# Nano_XBee.net
KiCad netlist of a schematic drawn in EAGLE
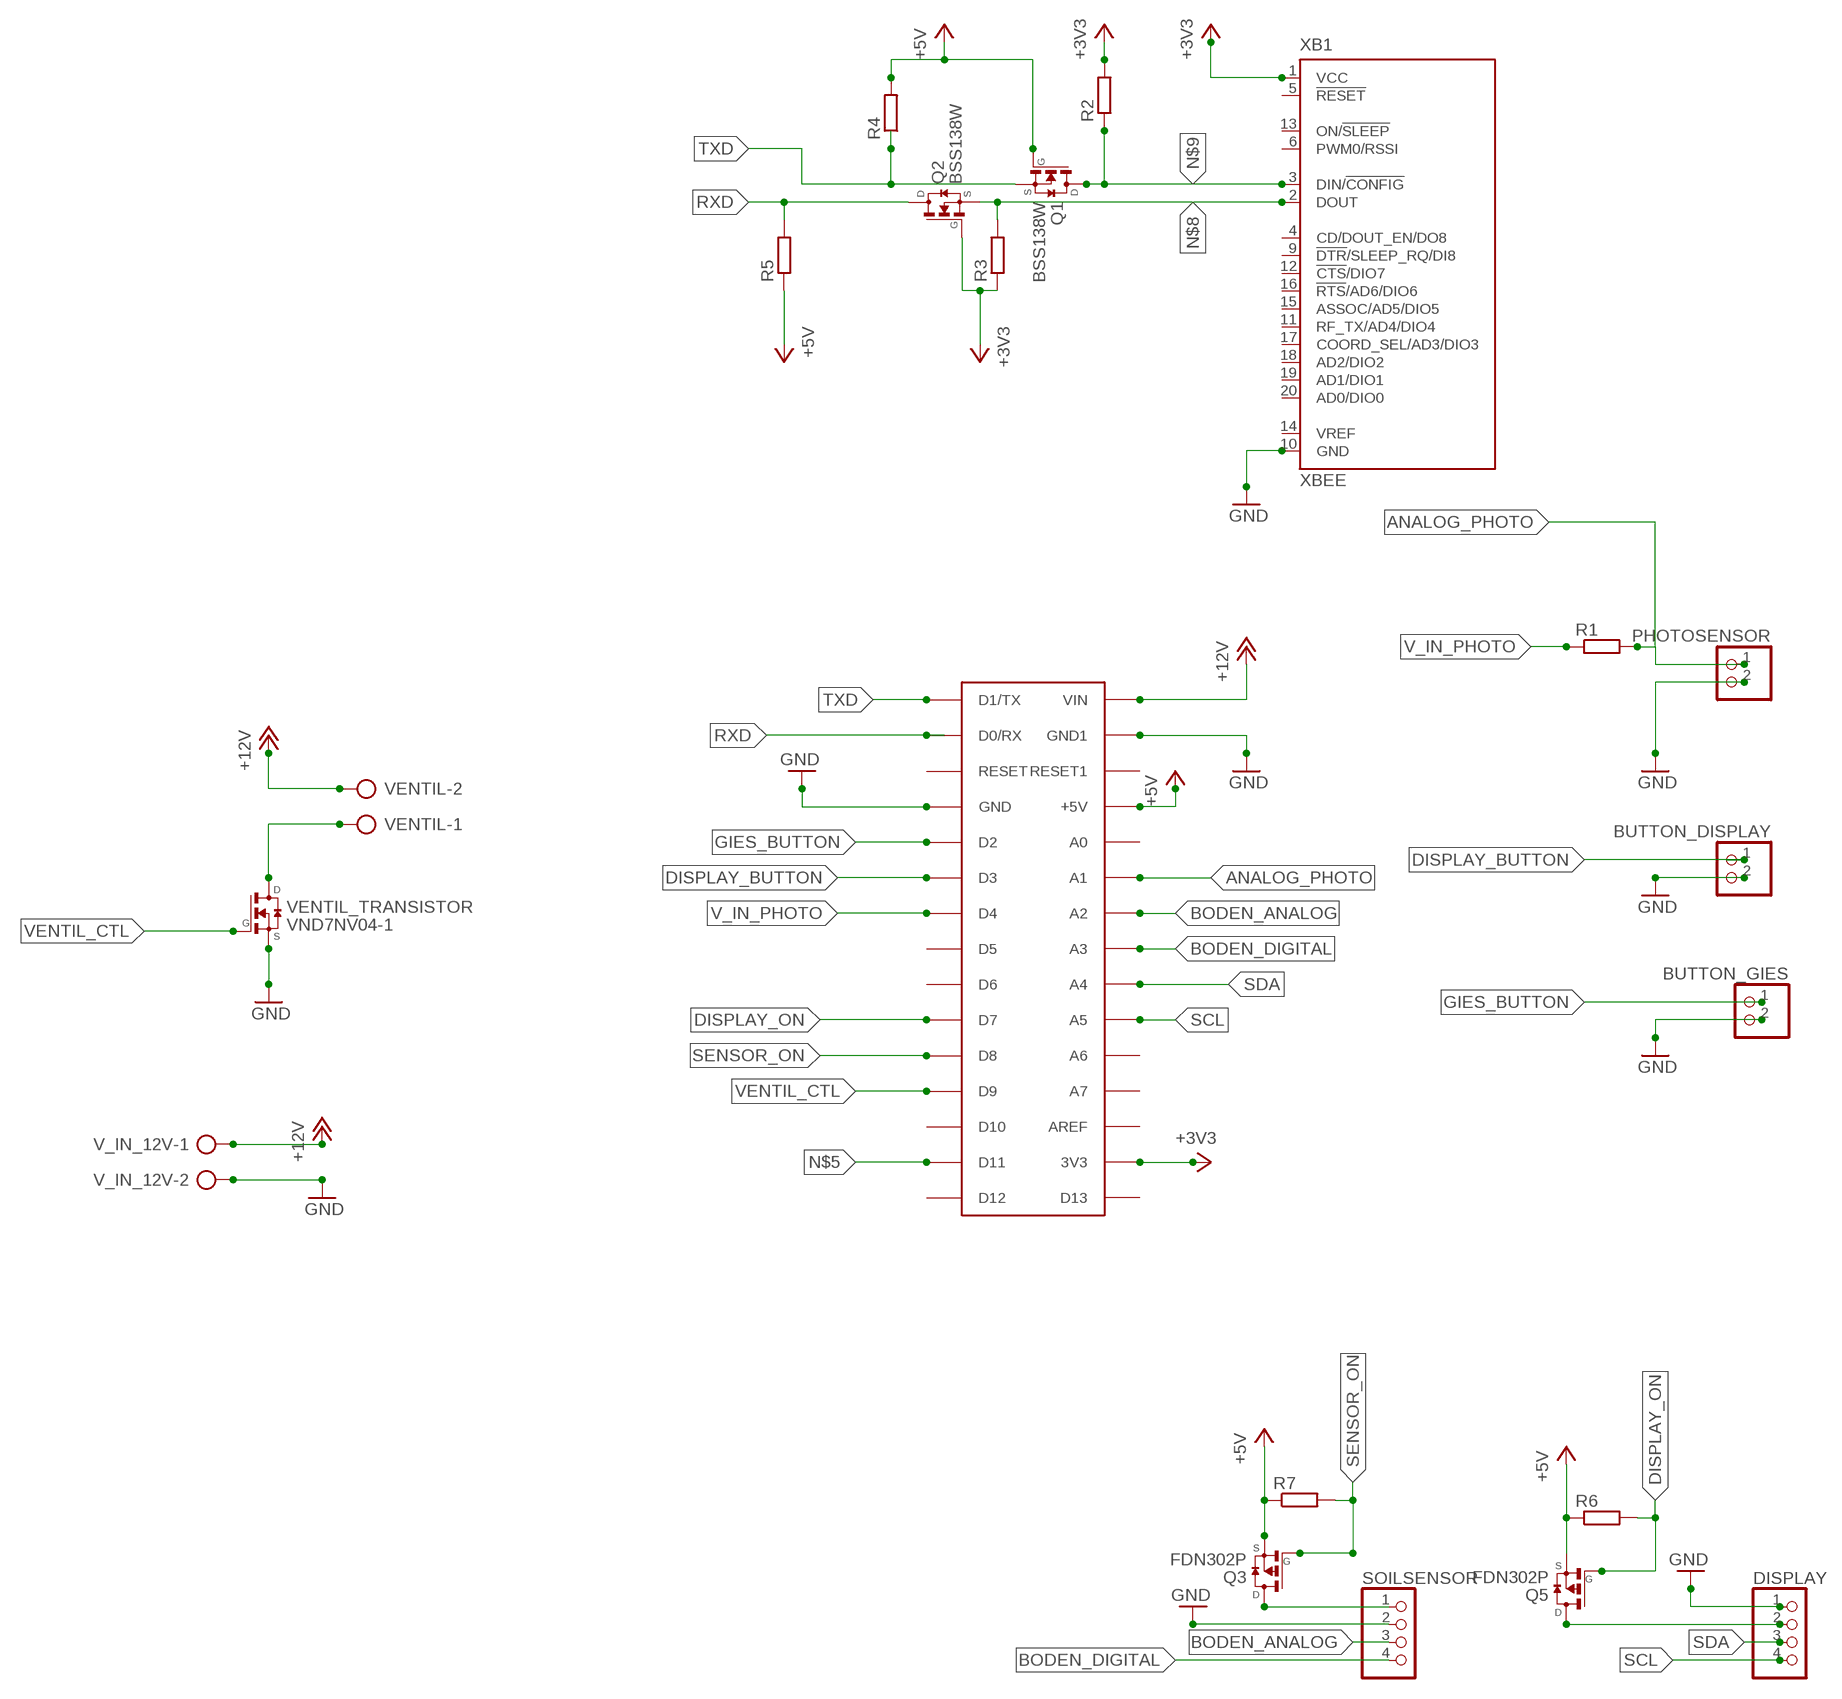
[diagram p0: schematic, sheet 1]

(export (version "E")
  (design (tool "Eeschema 10.0.6"))
  (components
    (comp (ref "BUTTON_DISPLAY")
      (value "PINHD-1X2")
      (footprint "eagle-import:1X02")
      (libsource (lib "eagle-import") (part "PINHD-1X2"))
    )
    (comp (ref "BUTTON_GIES")
      (value "PINHD-1X2")
      (footprint "eagle-import:1X02")
      (libsource (lib "eagle-import") (part "PINHD-1X2"))
    )
    (comp (ref "DISPLAY")
      (value "PINHD-1X4")
      (footprint "eagle-import:1X04")
      (libsource (lib "eagle-import") (part "PINHD-1X4"))
    )
    (comp (ref "PHOTOSENSOR")
      (value "PINHD-1X2")
      (footprint "eagle-import:1X02")
      (libsource (lib "eagle-import") (part "PINHD-1X2"))
    )
    (comp (ref "Q1")
      (value "BSS138W")
      (footprint "eagle-import:SOT323-R")
      (libsource (lib "eagle-import") (part "BSS138W"))
    )
    (comp (ref "Q2")
      (value "BSS138W")
      (footprint "eagle-import:SOT323-R")
      (libsource (lib "eagle-import") (part "BSS138W"))
    )
    (comp (ref "Q3")
      (value "FDN302P")
      (footprint "eagle-import:SSOT-3")
      (libsource (lib "eagle-import") (part "FDN302P"))
    )
    (comp (ref "Q5")
      (value "FDN302P")
      (footprint "eagle-import:SSOT-3")
      (libsource (lib "eagle-import") (part "FDN302P"))
    )
    (comp (ref "R1")
      (value "R-EU_0207/7")
      (footprint "eagle-import:0207_7")
      (libsource (lib "eagle-import") (part "R-EU_0207/7"))
    )
    (comp (ref "R2")
      (value "R-EU_M0805")
      (footprint "eagle-import:M0805")
      (libsource (lib "eagle-import") (part "R-EU_M0805"))
    )
    (comp (ref "R3")
      (value "R-EU_M0805")
      (footprint "eagle-import:M0805")
      (libsource (lib "eagle-import") (part "R-EU_M0805"))
    )
    (comp (ref "R4")
      (value "R-EU_M0805")
      (footprint "eagle-import:M0805")
      (libsource (lib "eagle-import") (part "R-EU_M0805"))
    )
    (comp (ref "R5")
      (value "R-EU_M0805")
      (footprint "eagle-import:M0805")
      (libsource (lib "eagle-import") (part "R-EU_M0805"))
    )
    (comp (ref "R6")
      (value "R-EU_M0805")
      (footprint "eagle-import:M0805")
      (libsource (lib "eagle-import") (part "R-EU_M0805"))
    )
    (comp (ref "R7")
      (value "R-EU_M0805")
      (footprint "eagle-import:M0805")
      (libsource (lib "eagle-import") (part "R-EU_M0805"))
    )
    (comp (ref "SOILSENSOR")
      (value "PINHD-1X4")
      (footprint "eagle-import:1X04")
      (libsource (lib "eagle-import") (part "PINHD-1X4"))
    )
    (comp (ref "U$1")
      (value "ARDUINONANO")
      (footprint "eagle-import:PDIP-32")
      (libsource (lib "eagle-import") (part "ARDUINONANO"))
    )
    (comp (ref "VENTIL")
      (value "AK500/2")
      (footprint "eagle-import:AK500_2")
      (libsource (lib "eagle-import") (part "AK500/2"))
    )
    (comp (ref "VENTIL_TRANSISTOR")
      (value "VND7NV04-1")
      (footprint "eagle-import:IPAK")
      (libsource (lib "eagle-import") (part "VND7NV04-1"))
    )
    (comp (ref "V_IN_12V")
      (value "AK500/2")
      (footprint "eagle-import:AK500_2")
      (libsource (lib "eagle-import") (part "AK500/2"))
    )
    (comp (ref "XB1")
      (value "XBEE")
      (footprint "eagle-import:XBEE")
      (fields (field (name "MPN") "XBP24-Z7UIT-004"))
      (libsource (lib "eagle-import") (part "XBEE"))
    )
  )
  (nets
    (net (code "1") (name "+3V3") (class "Default")
      (node (ref "Q2") (pin "1") (pinfunction "G_1") (pintype "passive"))
      (node (ref "R2") (pin "2") (pinfunction "2_2") (pintype "passive"))
      (node (ref "R3") (pin "1") (pinfunction "1_1") (pintype "passive"))
      (node (ref "U$1") (pin "3V3") (pinfunction "3V3_3V3") (pintype "bidirectional"))
      (node (ref "XB1") (pin "1") (pinfunction "VCC_1") (pintype "power_in"))
    )
    (net (code "2") (name "+5V") (class "Default")
      (node (ref "Q1") (pin "1") (pinfunction "G_1") (pintype "passive"))
      (node (ref "Q3") (pin "2") (pinfunction "S_2") (pintype "passive"))
      (node (ref "Q5") (pin "2") (pinfunction "S_2") (pintype "passive"))
      (node (ref "R4") (pin "2") (pinfunction "2_2") (pintype "passive"))
      (node (ref "R5") (pin "1") (pinfunction "1_1") (pintype "passive"))
      (node (ref "R6") (pin "1") (pinfunction "1_1") (pintype "passive"))
      (node (ref "R7") (pin "1") (pinfunction "1_1") (pintype "passive"))
      (node (ref "U$1") (pin "+5V") (pinfunction "+5V_+5V") (pintype "bidirectional"))
    )
    (net (code "3") (name "+12V") (class "Default")
      (node (ref "U$1") (pin "VIN") (pinfunction "VIN_VIN") (pintype "bidirectional"))
      (node (ref "VENTIL") (pin "2") (pinfunction "KL_2") (pintype "passive"))
      (node (ref "V_IN_12V") (pin "1") (pinfunction "KL_1") (pintype "passive"))
    )
    (net (code "4") (name "ANALOG_PHOTO") (class "Default")
      (node (ref "PHOTOSENSOR") (pin "1") (pinfunction "1_1") (pintype "passive"))
      (node (ref "R1") (pin "2") (pinfunction "2_2") (pintype "passive"))
      (node (ref "U$1") (pin "A1") (pinfunction "A1_A1") (pintype "bidirectional"))
    )
    (net (code "5") (name "BODEN_ANALOG") (class "Default")
      (node (ref "SOILSENSOR") (pin "3") (pinfunction "3_3") (pintype "passive"))
      (node (ref "U$1") (pin "A2") (pinfunction "A2_A2") (pintype "bidirectional"))
    )
    (net (code "6") (name "BODEN_DIGITAL") (class "Default")
      (node (ref "SOILSENSOR") (pin "4") (pinfunction "4_4") (pintype "passive"))
      (node (ref "U$1") (pin "A3") (pinfunction "A3_A3") (pintype "bidirectional"))
    )
    (net (code "7") (name "DISPLAY_BUTTON") (class "Default")
      (node (ref "BUTTON_DISPLAY") (pin "1") (pinfunction "1_1") (pintype "passive"))
      (node (ref "U$1") (pin "D3") (pinfunction "D3_D3") (pintype "bidirectional"))
    )
    (net (code "8") (name "DISPLAY_ON") (class "Default")
      (node (ref "Q5") (pin "1") (pinfunction "G_1") (pintype "passive"))
      (node (ref "R6") (pin "2") (pinfunction "2_2") (pintype "passive"))
      (node (ref "U$1") (pin "D7") (pinfunction "D7_D7") (pintype "bidirectional"))
    )
    (net (code "9") (name "GIES_BUTTON") (class "Default")
      (node (ref "BUTTON_GIES") (pin "1") (pinfunction "1_1") (pintype "passive"))
      (node (ref "U$1") (pin "D2") (pinfunction "D2_D2") (pintype "bidirectional"))
    )
    (net (code "10") (name "GND") (class "Default")
      (node (ref "BUTTON_DISPLAY") (pin "2") (pinfunction "2_2") (pintype "passive"))
      (node (ref "BUTTON_GIES") (pin "2") (pinfunction "2_2") (pintype "passive"))
      (node (ref "DISPLAY") (pin "1") (pinfunction "1_1") (pintype "passive"))
      (node (ref "PHOTOSENSOR") (pin "2") (pinfunction "2_2") (pintype "passive"))
      (node (ref "SOILSENSOR") (pin "2") (pinfunction "2_2") (pintype "passive"))
      (node (ref "U$1") (pin "GND") (pinfunction "GND_GND") (pintype "bidirectional"))
      (node (ref "U$1") (pin "GND1") (pinfunction "GND1_GND1") (pintype "bidirectional"))
      (node (ref "VENTIL_TRANSISTOR") (pin "3") (pinfunction "S_3") (pintype "passive"))
      (node (ref "V_IN_12V") (pin "2") (pinfunction "KL_2") (pintype "passive"))
      (node (ref "XB1") (pin "10") (pinfunction "GND_10") (pintype "power_in"))
    )
    (net (code "11") (name "N$5") (class "Default")
      (node (ref "U$1") (pin "D11") (pinfunction "D11_D11") (pintype "bidirectional"))
    )
    (net (code "12") (name "N$8") (class "Default")
      (node (ref "Q2") (pin "2") (pinfunction "S_2") (pintype "passive"))
      (node (ref "R3") (pin "2") (pinfunction "2_2") (pintype "passive"))
      (node (ref "XB1") (pin "2") (pinfunction "DOUT_2") (pintype "output"))
    )
    (net (code "13") (name "N$9") (class "Default")
      (node (ref "Q1") (pin "3") (pinfunction "D_3") (pintype "passive"))
      (node (ref "R2") (pin "1") (pinfunction "1_1") (pintype "passive"))
      (node (ref "XB1") (pin "3") (pinfunction "DIN/~{CONFIG}_3") (pintype "input"))
    )
    (net (code "14") (name "Net-(Q3-D)") (class "Default")
      (node (ref "Q3") (pin "3") (pinfunction "D_3") (pintype "passive"))
      (node (ref "SOILSENSOR") (pin "1") (pinfunction "1_1") (pintype "passive"))
    )
    (net (code "15") (name "Net-(Q5-D)") (class "Default")
      (node (ref "DISPLAY") (pin "2") (pinfunction "2_2") (pintype "passive"))
      (node (ref "Q5") (pin "3") (pinfunction "D_3") (pintype "passive"))
    )
    (net (code "16") (name "Net-(VENTILA-KL)") (class "Default")
      (node (ref "VENTIL") (pin "1") (pinfunction "KL_1") (pintype "passive"))
      (node (ref "VENTIL_TRANSISTOR") (pin "2") (pinfunction "D_2") (pintype "passive"))
    )
    (net (code "17") (name "RXD") (class "Default")
      (node (ref "Q2") (pin "3") (pinfunction "D_3") (pintype "passive"))
      (node (ref "R5") (pin "2") (pinfunction "2_2") (pintype "passive"))
      (node (ref "U$1") (pin "D0/RX") (pinfunction "D0/RX_D0/RX") (pintype "bidirectional"))
    )
    (net (code "18") (name "SCL") (class "Default")
      (node (ref "DISPLAY") (pin "4") (pinfunction "4_4") (pintype "passive"))
      (node (ref "U$1") (pin "A5") (pinfunction "A5_A5") (pintype "bidirectional"))
    )
    (net (code "19") (name "SDA") (class "Default")
      (node (ref "DISPLAY") (pin "3") (pinfunction "3_3") (pintype "passive"))
      (node (ref "U$1") (pin "A4") (pinfunction "A4_A4") (pintype "bidirectional"))
    )
    (net (code "20") (name "SENSOR_ON") (class "Default")
      (node (ref "Q3") (pin "1") (pinfunction "G_1") (pintype "passive"))
      (node (ref "R7") (pin "2") (pinfunction "2_2") (pintype "passive"))
      (node (ref "U$1") (pin "D8") (pinfunction "D8_D8") (pintype "bidirectional"))
    )
    (net (code "21") (name "TXD") (class "Default")
      (node (ref "Q1") (pin "2") (pinfunction "S_2") (pintype "passive"))
      (node (ref "R4") (pin "1") (pinfunction "1_1") (pintype "passive"))
      (node (ref "U$1") (pin "D1/TX") (pinfunction "D1/TX_D1/TX") (pintype "bidirectional"))
    )
    (net (code "22") (name "VENTIL_CTL") (class "Default")
      (node (ref "U$1") (pin "D9") (pinfunction "D9_D9") (pintype "bidirectional"))
      (node (ref "VENTIL_TRANSISTOR") (pin "1") (pinfunction "G_1") (pintype "passive"))
    )
    (net (code "23") (name "V_IN_PHOTO") (class "Default")
      (node (ref "R1") (pin "1") (pinfunction "1_1") (pintype "passive"))
      (node (ref "U$1") (pin "D4") (pinfunction "D4_D4") (pintype "bidirectional"))
    )
    (net (code "24") (name "unconnected-(U$1-PadA0)") (class "Default")
      (node (ref "U$1") (pin "A0") (pinfunction "A0_A0") (pintype "bidirectional"))
    )
    (net (code "25") (name "unconnected-(U$1-PadA6)") (class "Default")
      (node (ref "U$1") (pin "A6") (pinfunction "A6_A6") (pintype "bidirectional"))
    )
    (net (code "26") (name "unconnected-(U$1-PadA7)") (class "Default")
      (node (ref "U$1") (pin "A7") (pinfunction "A7_A7") (pintype "bidirectional"))
    )
    (net (code "27") (name "unconnected-(U$1-PadAREF)") (class "Default")
      (node (ref "U$1") (pin "AREF") (pinfunction "AREF_AREF") (pintype "bidirectional"))
    )
    (net (code "28") (name "unconnected-(U$1-PadD5)") (class "Default")
      (node (ref "U$1") (pin "D5") (pinfunction "D5_D5") (pintype "bidirectional"))
    )
    (net (code "29") (name "unconnected-(U$1-PadD6)") (class "Default")
      (node (ref "U$1") (pin "D6") (pinfunction "D6_D6") (pintype "bidirectional"))
    )
    (net (code "30") (name "unconnected-(U$1-PadD10)") (class "Default")
      (node (ref "U$1") (pin "D10") (pinfunction "D10_D10") (pintype "bidirectional"))
    )
    (net (code "31") (name "unconnected-(U$1-PadD12)") (class "Default")
      (node (ref "U$1") (pin "D12") (pinfunction "D12_D12") (pintype "bidirectional"))
    )
    (net (code "32") (name "unconnected-(U$1-PadD13)") (class "Default")
      (node (ref "U$1") (pin "D13") (pinfunction "D13_D13") (pintype "bidirectional"))
    )
    (net (code "33") (name "unconnected-(U$1-PadRESET)") (class "Default")
      (node (ref "U$1") (pin "RESET") (pinfunction "RESET_RESET") (pintype "bidirectional"))
    )
    (net (code "34") (name "unconnected-(U$1-PadRESET1)") (class "Default")
      (node (ref "U$1") (pin "RESET1") (pinfunction "RESET1_RESET1") (pintype "bidirectional"))
    )
    (net (code "35") (name "unconnected-(XB1-AD0{slash}DIO0-Pad20)") (class "Default")
      (node (ref "XB1") (pin "20") (pinfunction "AD0/DIO0_20") (pintype "bidirectional"))
    )
    (net (code "36") (name "unconnected-(XB1-AD1{slash}DIO1-Pad19)") (class "Default")
      (node (ref "XB1") (pin "19") (pinfunction "AD1/DIO1_19") (pintype "bidirectional"))
    )
    (net (code "37") (name "unconnected-(XB1-AD2{slash}DIO2-Pad18)") (class "Default")
      (node (ref "XB1") (pin "18") (pinfunction "AD2/DIO2_18") (pintype "bidirectional"))
    )
    (net (code "38") (name "unconnected-(XB1-ASSOC{slash}AD5{slash}DIO5-Pad15)") (class "Default")
      (node (ref "XB1") (pin "15") (pinfunction "ASSOC/AD5/DIO5_15") (pintype "bidirectional"))
    )
    (net (code "39") (name "unconnected-(XB1-CD{slash}DOUT_EN{slash}DO8-Pad4)") (class "Default")
      (node (ref "XB1") (pin "4") (pinfunction "CD/DOUT_EN/DO8_4") (pintype "output"))
    )
    (net (code "40") (name "unconnected-(XB1-COORD_SEL{slash}AD3{slash}DIO3-Pad17)") (class "Default")
      (node (ref "XB1") (pin "17") (pinfunction "COORD_SEL/AD3/DIO3_17") (pintype "bidirectional"))
    )
    (net (code "41") (name "unconnected-(XB1-ON{slash}~{SLEEP}-Pad13)") (class "Default")
      (node (ref "XB1") (pin "13") (pinfunction "ON/~{SLEEP}_13") (pintype "output"))
    )
    (net (code "42") (name "unconnected-(XB1-PWM0{slash}RSSI-Pad6)") (class "Default")
      (node (ref "XB1") (pin "6") (pinfunction "PWM0/RSSI_6") (pintype "output"))
    )
    (net (code "43") (name "unconnected-(XB1-RF_TX{slash}AD4{slash}DIO4-Pad11)") (class "Default")
      (node (ref "XB1") (pin "11") (pinfunction "RF_TX/AD4/DIO4_11") (pintype "bidirectional"))
    )
    (net (code "44") (name "unconnected-(XB1-VREF-Pad14)") (class "Default")
      (node (ref "XB1") (pin "14") (pinfunction "VREF_14") (pintype "input"))
    )
    (net (code "45") (name "unconnected-(XB1-~{CTS}{slash}DIO7-Pad12)") (class "Default")
      (node (ref "XB1") (pin "12") (pinfunction "~{CTS}/DIO7_12") (pintype "bidirectional"))
    )
    (net (code "46") (name "unconnected-(XB1-~{DTR}{slash}SLEEP_RQ{slash}DI8-Pad9)") (class "Default")
      (node (ref "XB1") (pin "9") (pinfunction "~{DTR}/SLEEP_RQ/DI8_9") (pintype "bidirectional"))
    )
    (net (code "47") (name "unconnected-(XB1-~{RESET}-Pad5)") (class "Default")
      (node (ref "XB1") (pin "5") (pinfunction "~{RESET}_5") (pintype "input"))
    )
    (net (code "48") (name "unconnected-(XB1-~{RTS}{slash}AD6{slash}DIO6-Pad16)") (class "Default")
      (node (ref "XB1") (pin "16") (pinfunction "~{RTS}/AD6/DIO6_16") (pintype "bidirectional"))
    )
  )
)
